# working.net
KiCad netlist of a schematic drawn in EAGLE
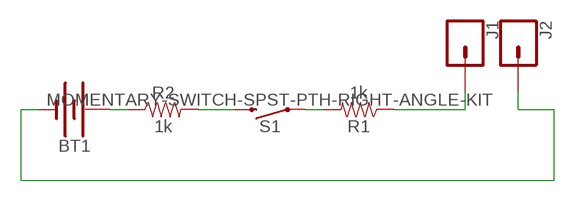
[diagram p0: schematic, sheet 1]

(export (version "E")
  (design (tool "Eeschema 10.0.6"))
  (components
    (comp (ref "BT1")
      (value "BATTERY-20MM_SMD_4LEGS")
      (footprint "eagle-import:BATTCON_20MM_4LEGS")
      (libsource (lib "eagle-import") (part "BATTERY-20MM_SMD_4LEGS"))
    )
    (comp (ref "J1")
      (value "CONN_01")
      (footprint "eagle-import:1X01")
      (libsource (lib "eagle-import") (part "CONN_01"))
    )
    (comp (ref "J2")
      (value "CONN_01")
      (footprint "eagle-import:1X01")
      (libsource (lib "eagle-import") (part "CONN_01"))
    )
    (comp (ref "R1")
      (value "1k")
      (footprint "eagle-import:AXIAL-0.3")
      (libsource (lib "eagle-import") (part "1KOHM-HORIZ-1/4W-1%"))
    )
    (comp (ref "R2")
      (value "1k")
      (footprint "eagle-import:AXIAL-0.3")
      (libsource (lib "eagle-import") (part "1KOHM-HORIZ-1/4W-1%"))
    )
    (comp (ref "S1")
      (value "MOMENTARY-SWITCH-SPST-PTH-RIGHT-ANGLE-KIT")
      (footprint "eagle-import:TACTILE_SWITCH_PTH_RIGHT_ANGLE_KIT")
      (libsource (lib "eagle-import") (part "MOMENTARY-SWITCH-SPST-PTH-RIGHT-ANGLE-KIT"))
    )
  )
  (nets
    (net (code "1") (name "Net-(BT1--)") (class "Default")
      (node (ref "BT1") (pin "NEGATIVE") (pinfunction "-_NEGATIVE") (pintype "power_in"))
      (node (ref "J2") (pin "1") (pinfunction "1_1") (pintype "passive"))
    )
    (net (code "2") (name "Net-(R1-1)") (class "Default")
      (node (ref "J1") (pin "1") (pinfunction "1_1") (pintype "passive"))
      (node (ref "R1") (pin "P$1") (pinfunction "1_P$1") (pintype "passive"))
    )
    (net (code "3") (name "Net-(R1-2)") (class "Default")
      (node (ref "R1") (pin "P$2") (pinfunction "2_P$2") (pintype "passive"))
      (node (ref "S1") (pin "1") (pinfunction "1_1") (pintype "passive"))
    )
    (net (code "4") (name "Net-(R2-1)") (class "Default")
      (node (ref "BT1") (pin "POSITIVE@1") (pinfunction "+_POSITIVE@1") (pintype "power_in"))
      (node (ref "BT1") (pin "POSITIVE@2") (pinfunction "+_POSITIVE@2") (pintype "power_in"))
      (node (ref "BT1") (pin "POSITIVE@3") (pinfunction "+_POSITIVE@3") (pintype "power_in"))
      (node (ref "BT1") (pin "POSITIVE@4") (pinfunction "+_POSITIVE@4") (pintype "power_in"))
      (node (ref "R2") (pin "P$1") (pinfunction "1_P$1") (pintype "passive"))
    )
    (net (code "5") (name "Net-(R2-2)") (class "Default")
      (node (ref "R2") (pin "P$2") (pinfunction "2_P$2") (pintype "passive"))
      (node (ref "S1") (pin "2") (pinfunction "2_2") (pintype "passive"))
    )
  )
)
